# Winter_v2.net
KiCad netlist of a schematic drawn in EAGLE
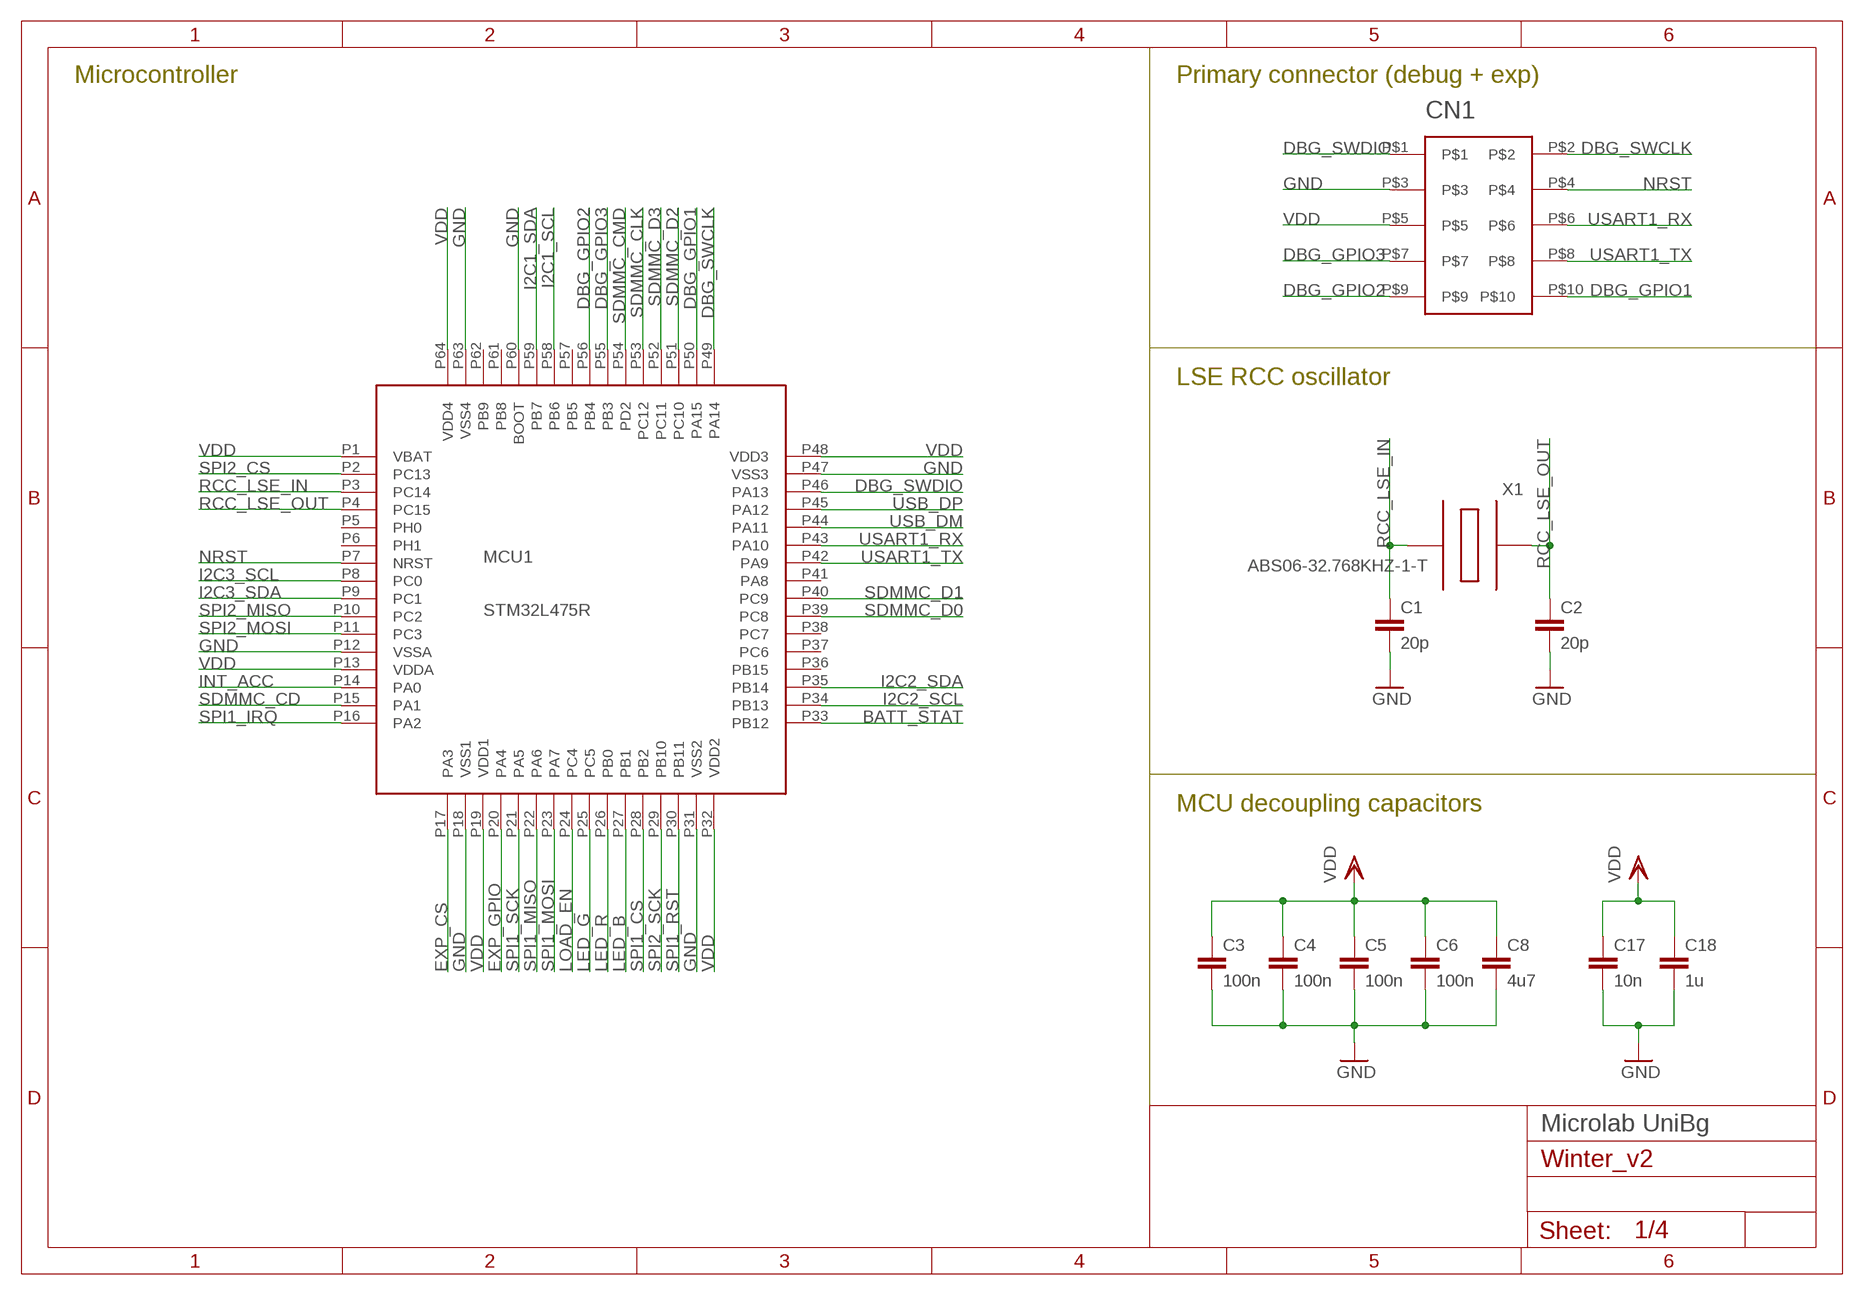
[diagram p0: schematic, sheet 1]
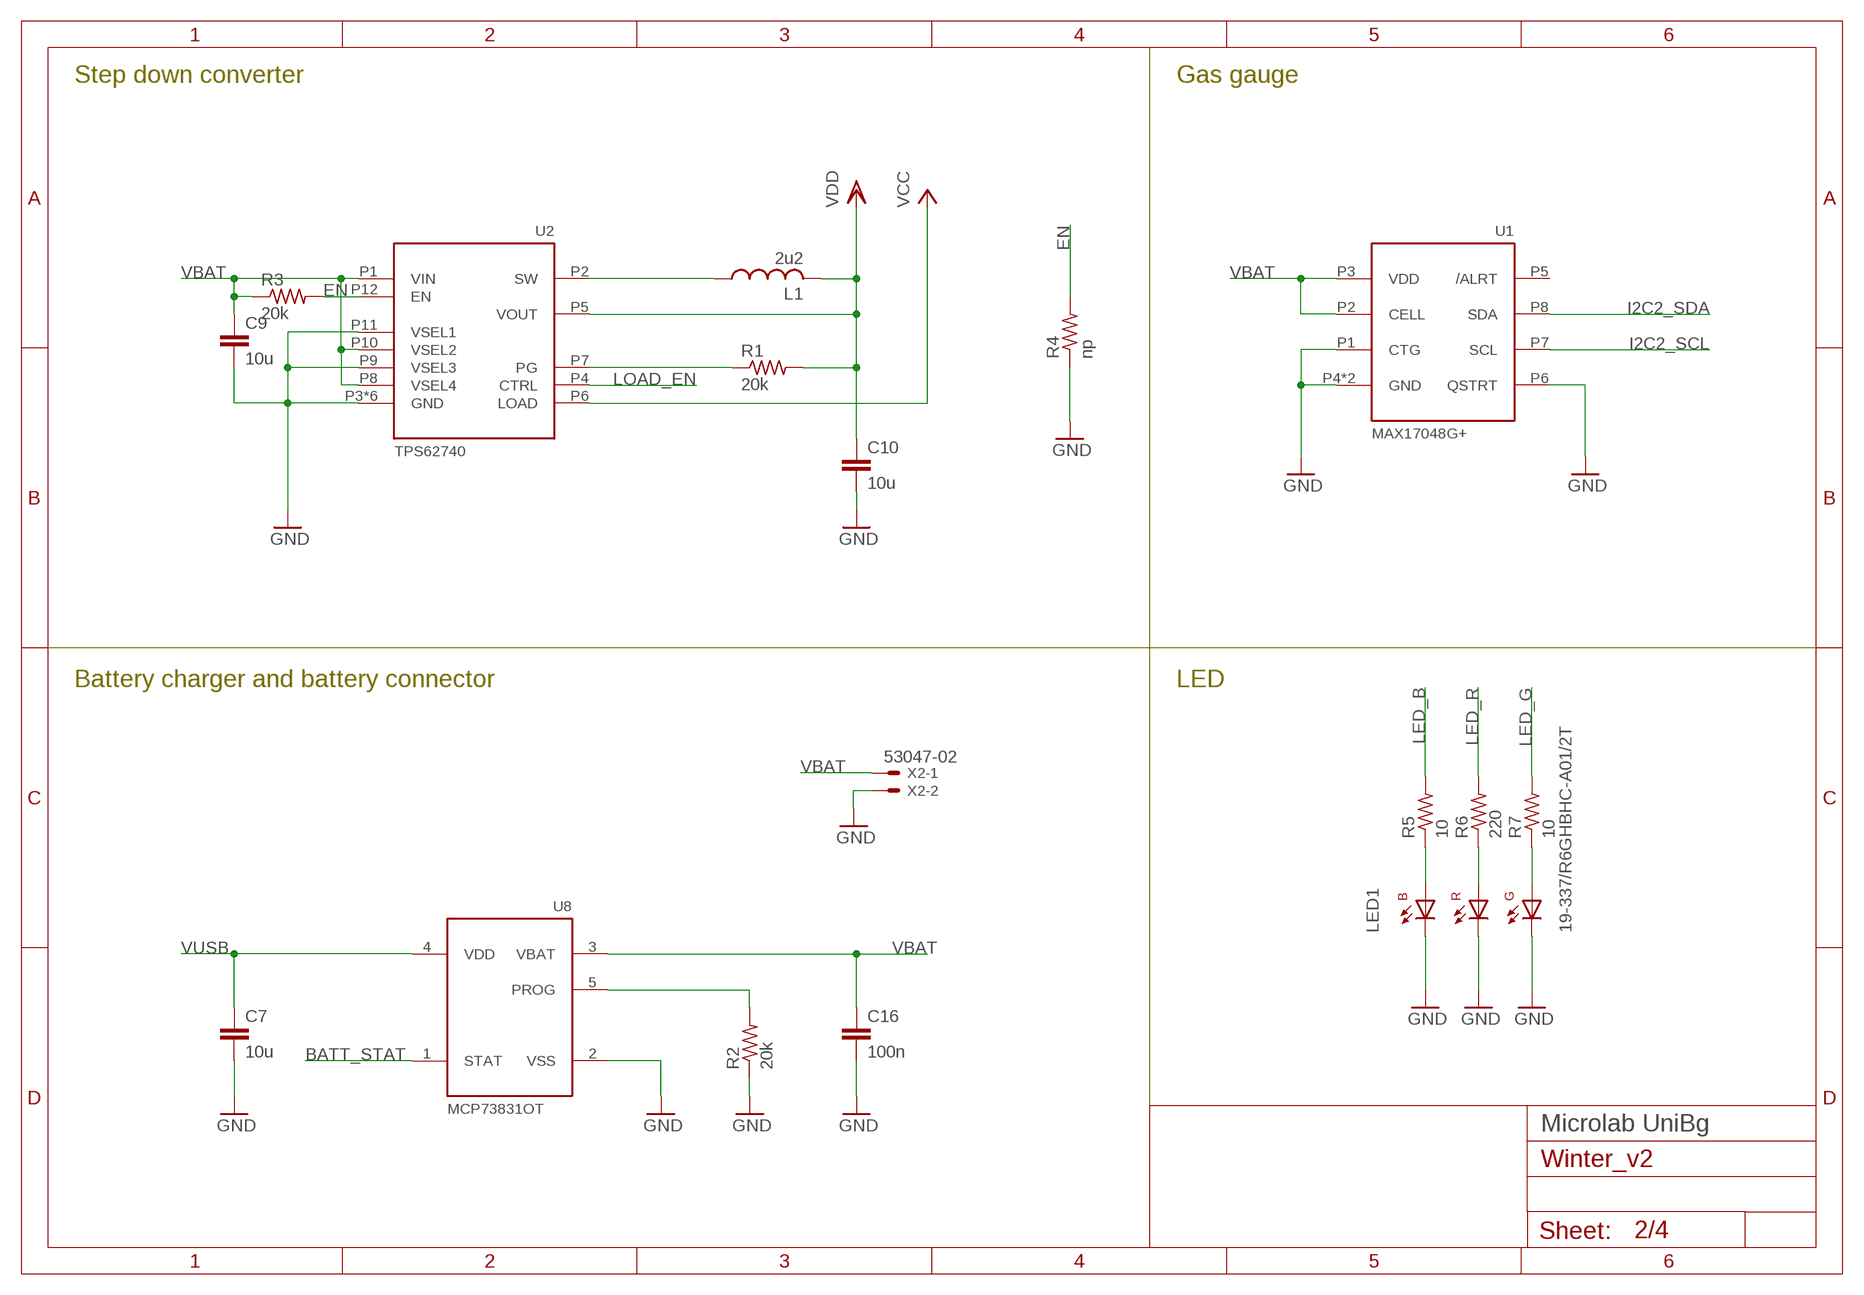
[diagram p1: schematic, sheet 2]
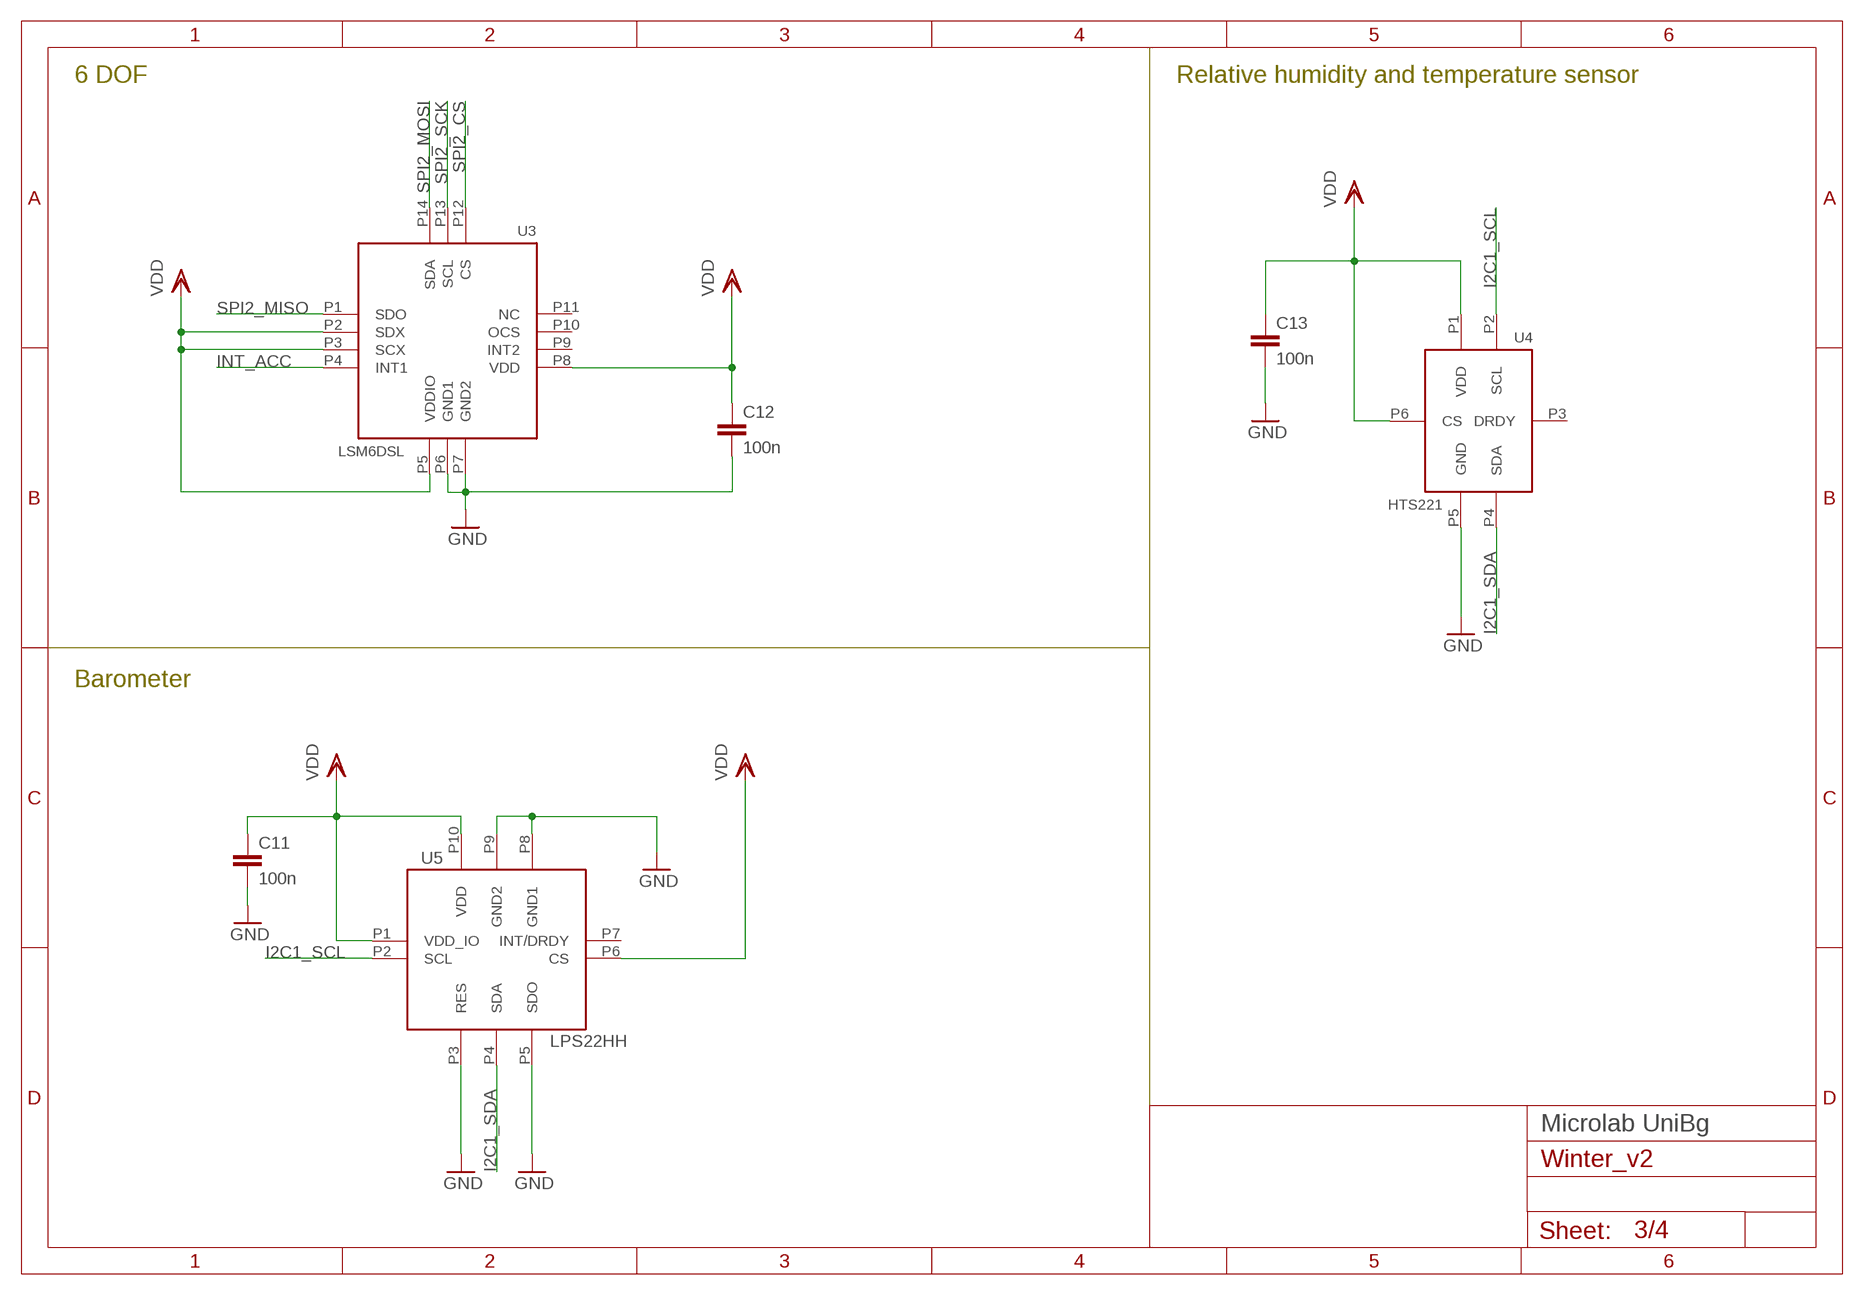
[diagram p2: schematic, sheet 3]
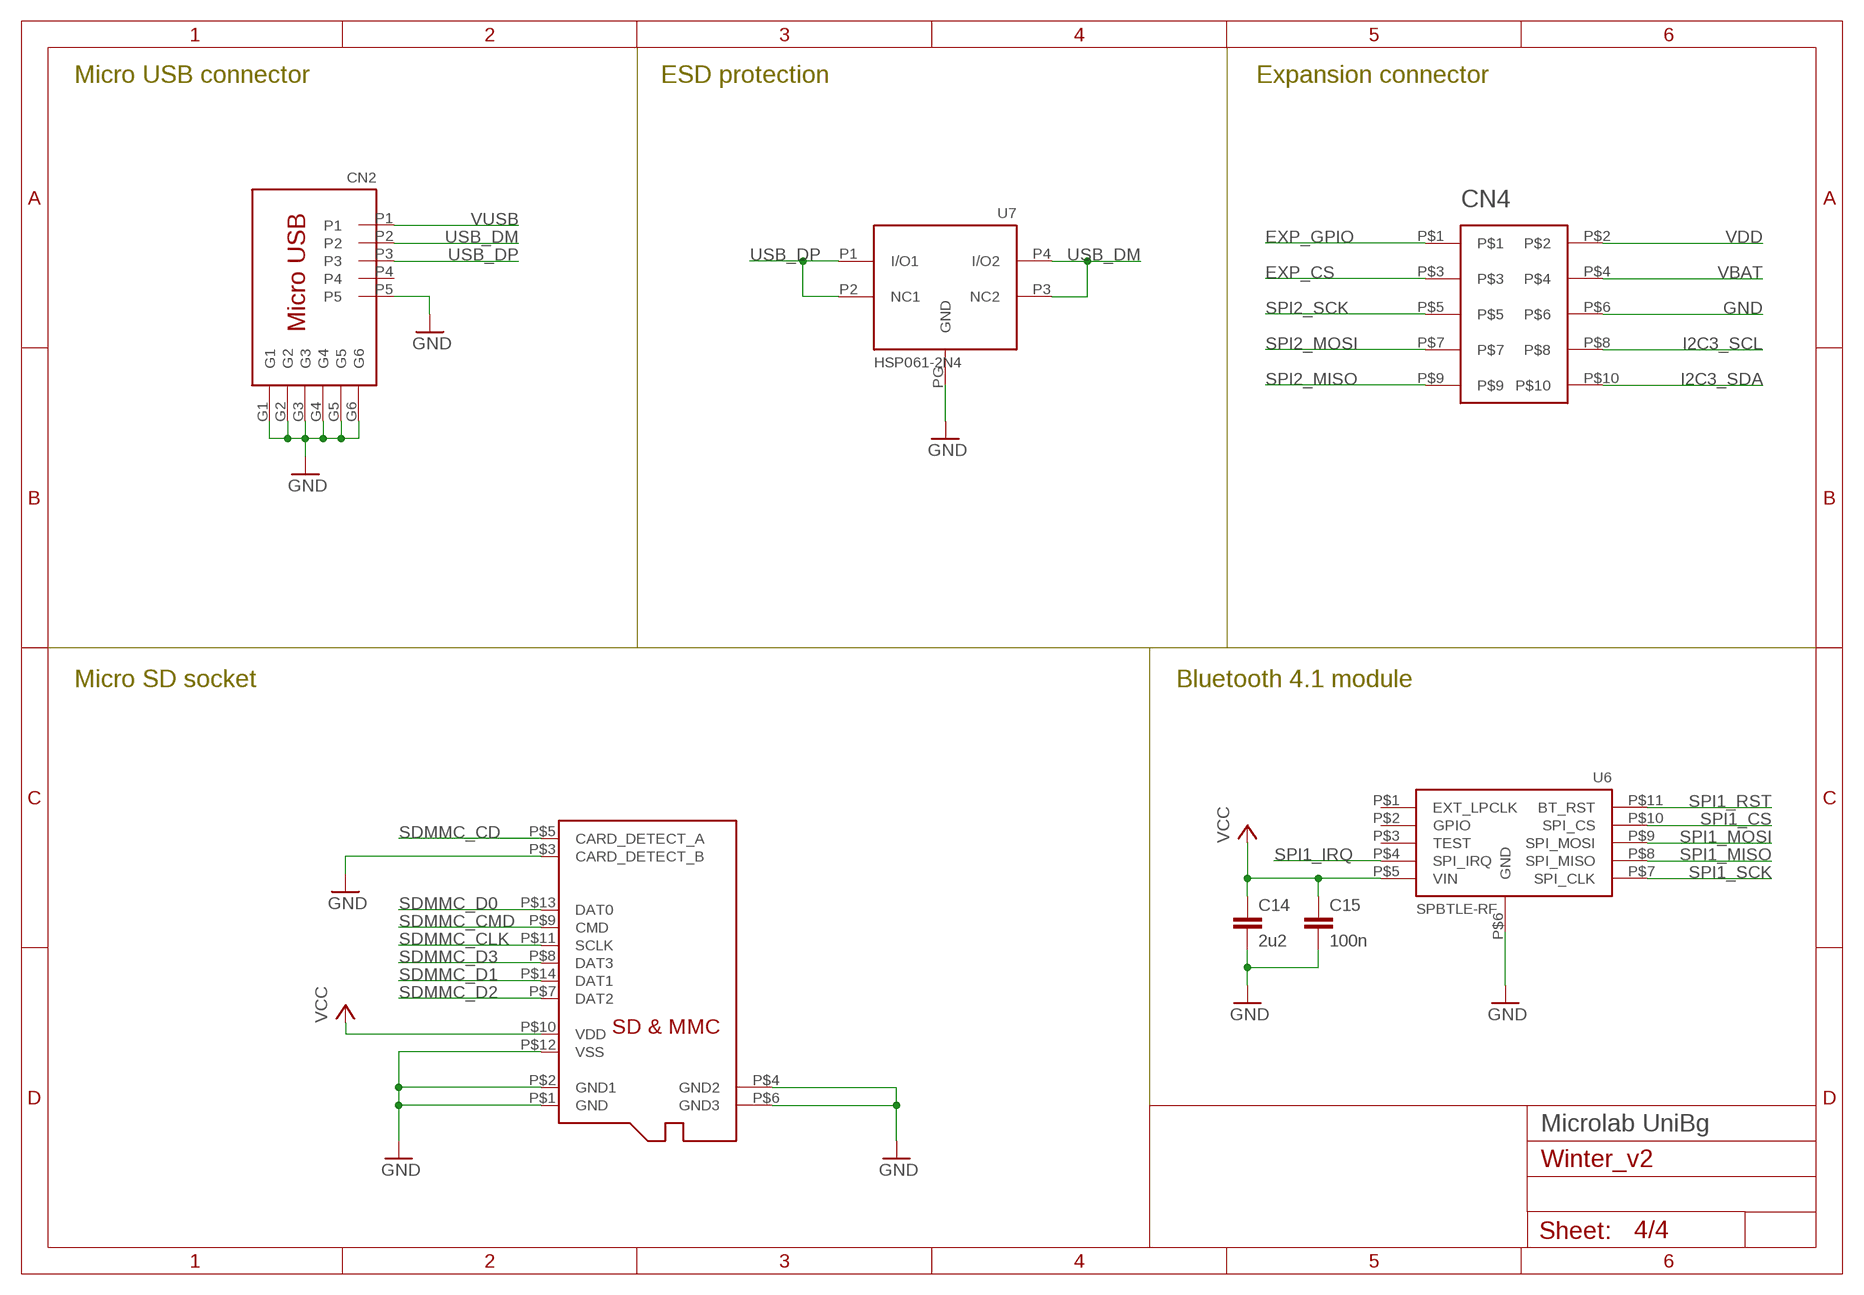
[diagram p3: schematic, sheet 4]

(export (version "E")
  (design (tool "Eeschema 10.0.6"))
  (components
    (comp (ref "C1")
      (value "20p")
      (footprint "eagle-import:C0402")
      (libsource (lib "eagle-import") (part "C0402"))
    )
    (comp (ref "C2")
      (value "20p")
      (footprint "eagle-import:C0402")
      (libsource (lib "eagle-import") (part "C0402"))
    )
    (comp (ref "C3")
      (value "100n")
      (footprint "eagle-import:C0402")
      (libsource (lib "eagle-import") (part "C0402"))
    )
    (comp (ref "C4")
      (value "100n")
      (footprint "eagle-import:C0402")
      (libsource (lib "eagle-import") (part "C0402"))
    )
    (comp (ref "C5")
      (value "100n")
      (footprint "eagle-import:C0402")
      (libsource (lib "eagle-import") (part "C0402"))
    )
    (comp (ref "C6")
      (value "100n")
      (footprint "eagle-import:C0402")
      (libsource (lib "eagle-import") (part "C0402"))
    )
    (comp (ref "C8")
      (value "4u7")
      (footprint "eagle-import:C0402")
      (libsource (lib "eagle-import") (part "C0402"))
    )
    (comp (ref "C17")
      (value "10n")
      (footprint "eagle-import:C0402")
      (libsource (lib "eagle-import") (part "C0402"))
    )
    (comp (ref "C18")
      (value "1u")
      (footprint "eagle-import:C0402")
      (libsource (lib "eagle-import") (part "C0402"))
    )
    (comp (ref "CN1")
      (value "FTSH-105TO")
      (footprint "eagle-import:FTSH-105-XX")
      (libsource (lib "eagle-import") (part "FTSH-105TO"))
    )
    (comp (ref "MCU1")
      (value "STM32L475R")
      (footprint "eagle-import:LQFP64")
      (libsource (lib "eagle-import") (part "STM32L475R"))
    )
    (comp (ref "X1")
      (value "ABS06-32.768KHZ-1-T")
      (footprint "eagle-import:ABS06")
      (libsource (lib "eagle-import") (part "ABS06-32.768KHZ-1-T"))
    )
    (comp (ref "C7")
      (value "10u")
      (footprint "eagle-import:C0603")
      (libsource (lib "eagle-import") (part "C0603"))
    )
    (comp (ref "C9")
      (value "10u")
      (footprint "eagle-import:C0603")
      (libsource (lib "eagle-import") (part "C0603"))
    )
    (comp (ref "C10")
      (value "10u")
      (footprint "eagle-import:C0603")
      (libsource (lib "eagle-import") (part "C0603"))
    )
    (comp (ref "C16")
      (value "100n")
      (footprint "eagle-import:C0402")
      (libsource (lib "eagle-import") (part "C0402"))
    )
    (comp (ref "L1")
      (value "2u2")
      (footprint "eagle-import:C01005")
      (libsource (lib "eagle-import") (part "74479276222C74479276222C"))
    )
    (comp (ref "LED1")
      (value "19-337/R6GHBHC-A01/2T")
      (footprint "eagle-import:19-337_R6GHBHC-A01_2T")
      (libsource (lib "eagle-import") (part "19-337/R6GHBHC-A01/2T"))
    )
    (comp (ref "R1")
      (value "20k")
      (footprint "eagle-import:0402")
      (libsource (lib "eagle-import") (part "R0402"))
    )
    (comp (ref "R2")
      (value "20k")
      (footprint "eagle-import:0402")
      (libsource (lib "eagle-import") (part "R0402"))
    )
    (comp (ref "R3")
      (value "20k")
      (footprint "eagle-import:0402")
      (libsource (lib "eagle-import") (part "R0402"))
    )
    (comp (ref "R4")
      (value "np")
      (footprint "eagle-import:0402")
      (libsource (lib "eagle-import") (part "R0402"))
    )
    (comp (ref "R5")
      (value "10")
      (footprint "eagle-import:0402")
      (libsource (lib "eagle-import") (part "R0402"))
    )
    (comp (ref "R6")
      (value "220")
      (footprint "eagle-import:0402")
      (libsource (lib "eagle-import") (part "R0402"))
    )
    (comp (ref "R7")
      (value "10")
      (footprint "eagle-import:0402")
      (libsource (lib "eagle-import") (part "R0402"))
    )
    (comp (ref "U1")
      (value "MAX17048G+")
      (footprint "eagle-import:TDFN8-2X2")
      (libsource (lib "eagle-import") (part "MAX17048G+"))
    )
    (comp (ref "U2")
      (value "TPS62740")
      (footprint "eagle-import:R-PWSON-N12")
      (libsource (lib "eagle-import") (part "TPS62740"))
    )
    (comp (ref "U8")
      (value "MCP73831OT")
      (footprint "eagle-import:SOT23-5L")
      (libsource (lib "eagle-import") (part "MCP73831OT"))
    )
    (comp (ref "X2")
      (value "53047-02")
      (footprint "eagle-import:53047-02")
      (fields (field (name "MF") "MOLEX") (field (name "MPN") "53047-0210"))
      (libsource (lib "eagle-import") (part "53?-02047"))
    )
    (comp (ref "C11")
      (value "100n")
      (footprint "eagle-import:C0402")
      (libsource (lib "eagle-import") (part "C0402"))
    )
    (comp (ref "C12")
      (value "100n")
      (footprint "eagle-import:C0402")
      (libsource (lib "eagle-import") (part "C0402"))
    )
    (comp (ref "C13")
      (value "100n")
      (footprint "eagle-import:C0402")
      (libsource (lib "eagle-import") (part "C0402"))
    )
    (comp (ref "U3")
      (value "LSM6DSL")
      (footprint "eagle-import:LGA-14L")
      (libsource (lib "eagle-import") (part "LSM6DSL"))
    )
    (comp (ref "U4")
      (value "HTS221")
      (footprint "eagle-import:HCLGA-6L")
      (libsource (lib "eagle-import") (part "HTS221"))
    )
    (comp (ref "U5")
      (value "LPS22HH")
      (footprint "eagle-import:HLGA-10L")
      (libsource (lib "eagle-import") (part "LPS22HH"))
    )
    (comp (ref "C14")
      (value "2u2")
      (footprint "eagle-import:C0402")
      (libsource (lib "eagle-import") (part "C0402"))
    )
    (comp (ref "C15")
      (value "100n")
      (footprint "eagle-import:C0402")
      (libsource (lib "eagle-import") (part "C0402"))
    )
    (comp (ref "CN2")
      (value "USB3075")
      (footprint "eagle-import:USB3075")
      (libsource (lib "eagle-import") (part "USB3075"))
    )
    (comp (ref "CN3")
      (value "MICRO_SD-5025700893")
      (footprint "eagle-import:5025700893")
      (libsource (lib "eagle-import") (part "MICRO_SD-5025700893"))
    )
    (comp (ref "CN4")
      (value "FTSH-105TO")
      (footprint "eagle-import:FTSH-105-XX")
      (libsource (lib "eagle-import") (part "FTSH-105TO"))
    )
    (comp (ref "U6")
      (value "SPBTLE-RF")
      (footprint "eagle-import:SPBTLE-RF")
      (libsource (lib "eagle-import") (part "SPBTLE-RF"))
    )
    (comp (ref "U7")
      (value "HSP061-2N4")
      (footprint "eagle-import:μQFN-4L")
      (libsource (lib "eagle-import") (part "HSP061-2N4"))
    )
  )
  (nets
    (net (code "1") (name "BATT_STAT") (class "Default")
      (node (ref "MCU1") (pin "P33") (pinfunction "PB12_P33") (pintype "bidirectional"))
      (node (ref "U8") (pin "1") (pinfunction "STAT_1") (pintype "bidirectional"))
    )
    (net (code "2") (name "DBG_GPIO1") (class "Default")
      (node (ref "CN1") (pin "P$10") (pinfunction "P$10_P$10") (pintype "bidirectional"))
      (node (ref "MCU1") (pin "P50") (pinfunction "PA15_P50") (pintype "bidirectional"))
    )
    (net (code "3") (name "DBG_GPIO2") (class "Default")
      (node (ref "CN1") (pin "P$9") (pinfunction "P$9_P$9") (pintype "bidirectional"))
      (node (ref "MCU1") (pin "P56") (pinfunction "PB4_P56") (pintype "bidirectional"))
    )
    (net (code "4") (name "DBG_GPIO3") (class "Default")
      (node (ref "CN1") (pin "P$7") (pinfunction "P$7_P$7") (pintype "bidirectional"))
      (node (ref "MCU1") (pin "P55") (pinfunction "PB3_P55") (pintype "bidirectional"))
    )
    (net (code "5") (name "DBG_SWCLK") (class "Default")
      (node (ref "CN1") (pin "P$2") (pinfunction "P$2_P$2") (pintype "bidirectional"))
      (node (ref "MCU1") (pin "P49") (pinfunction "PA14_P49") (pintype "bidirectional"))
    )
    (net (code "6") (name "DBG_SWDIO") (class "Default")
      (node (ref "CN1") (pin "P$1") (pinfunction "P$1_P$1") (pintype "bidirectional"))
      (node (ref "MCU1") (pin "P46") (pinfunction "PA13_P46") (pintype "bidirectional"))
    )
    (net (code "7") (name "EN") (class "Default")
      (node (ref "R3") (pin "P$2") (pinfunction "2_P$2") (pintype "passive"))
      (node (ref "R4") (pin "P$2") (pinfunction "2_P$2") (pintype "passive"))
      (node (ref "U2") (pin "P12") (pinfunction "EN_P12") (pintype "bidirectional"))
    )
    (net (code "8") (name "EXP_CS") (class "Default")
      (node (ref "CN4") (pin "P$3") (pinfunction "P$3_P$3") (pintype "bidirectional"))
      (node (ref "MCU1") (pin "P17") (pinfunction "PA3_P17") (pintype "bidirectional"))
    )
    (net (code "9") (name "EXP_GPIO") (class "Default")
      (node (ref "CN4") (pin "P$1") (pinfunction "P$1_P$1") (pintype "bidirectional"))
      (node (ref "MCU1") (pin "P20") (pinfunction "PA4_P20") (pintype "bidirectional"))
    )
    (net (code "10") (name "GND") (class "Default")
      (node (ref "C1") (pin "P$2") (pinfunction "2_P$2") (pintype "passive"))
      (node (ref "C10") (pin "P$2") (pinfunction "2_P$2") (pintype "passive"))
      (node (ref "C11") (pin "P$2") (pinfunction "2_P$2") (pintype "passive"))
      (node (ref "C12") (pin "P$2") (pinfunction "2_P$2") (pintype "passive"))
      (node (ref "C13") (pin "P$2") (pinfunction "2_P$2") (pintype "passive"))
      (node (ref "C14") (pin "P$2") (pinfunction "2_P$2") (pintype "passive"))
      (node (ref "C15") (pin "P$2") (pinfunction "2_P$2") (pintype "passive"))
      (node (ref "C16") (pin "P$2") (pinfunction "2_P$2") (pintype "passive"))
      (node (ref "C17") (pin "P$2") (pinfunction "2_P$2") (pintype "passive"))
      (node (ref "C18") (pin "P$2") (pinfunction "2_P$2") (pintype "passive"))
      (node (ref "C2") (pin "P$2") (pinfunction "2_P$2") (pintype "passive"))
      (node (ref "C3") (pin "P$2") (pinfunction "2_P$2") (pintype "passive"))
      (node (ref "C4") (pin "P$2") (pinfunction "2_P$2") (pintype "passive"))
      (node (ref "C5") (pin "P$2") (pinfunction "2_P$2") (pintype "passive"))
      (node (ref "C6") (pin "P$2") (pinfunction "2_P$2") (pintype "passive"))
      (node (ref "C7") (pin "P$2") (pinfunction "2_P$2") (pintype "passive"))
      (node (ref "C8") (pin "P$2") (pinfunction "2_P$2") (pintype "passive"))
      (node (ref "C9") (pin "P$2") (pinfunction "2_P$2") (pintype "passive"))
      (node (ref "CN1") (pin "P$3") (pinfunction "P$3_P$3") (pintype "bidirectional"))
      (node (ref "CN2") (pin "G1") (pinfunction "G1_G1") (pintype "bidirectional"))
      (node (ref "CN2") (pin "G2") (pinfunction "G2_G2") (pintype "bidirectional"))
      (node (ref "CN2") (pin "G3") (pinfunction "G3_G3") (pintype "bidirectional"))
      (node (ref "CN2") (pin "G4") (pinfunction "G4_G4") (pintype "bidirectional"))
      (node (ref "CN2") (pin "G5") (pinfunction "G5_G5") (pintype "bidirectional"))
      (node (ref "CN2") (pin "G6") (pinfunction "G6_G6") (pintype "bidirectional"))
      (node (ref "CN2") (pin "P5") (pinfunction "P5_P5") (pintype "bidirectional"))
      (node (ref "CN3") (pin "P$1") (pinfunction "GND_P$1") (pintype "power_in"))
      (node (ref "CN3") (pin "P$12") (pinfunction "VSS_P$12") (pintype "power_in"))
      (node (ref "CN3") (pin "P$2") (pinfunction "GND1_P$2") (pintype "power_in"))
      (node (ref "CN3") (pin "P$3") (pinfunction "CARD_DETECT_B_P$3") (pintype "passive"))
      (node (ref "CN3") (pin "P$4") (pinfunction "GND2_P$4") (pintype "bidirectional"))
      (node (ref "CN3") (pin "P$6") (pinfunction "GND3_P$6") (pintype "bidirectional"))
      (node (ref "CN4") (pin "P$6") (pinfunction "P$6_P$6") (pintype "bidirectional"))
      (node (ref "LED1") (pin "P$1") (pinfunction "CB_P$1") (pintype "passive"))
      (node (ref "LED1") (pin "P$2") (pinfunction "CR_P$2") (pintype "passive"))
      (node (ref "LED1") (pin "P$3") (pinfunction "CG_P$3") (pintype "passive"))
      (node (ref "MCU1") (pin "P12") (pinfunction "VSSA_P12") (pintype "bidirectional"))
      (node (ref "MCU1") (pin "P18") (pinfunction "VSS1_P18") (pintype "bidirectional"))
      (node (ref "MCU1") (pin "P31") (pinfunction "VSS2_P31") (pintype "bidirectional"))
      (node (ref "MCU1") (pin "P47") (pinfunction "VSS3_P47") (pintype "bidirectional"))
      (node (ref "MCU1") (pin "P60") (pinfunction "BOOT_P60") (pintype "bidirectional"))
      (node (ref "MCU1") (pin "P63") (pinfunction "VSS4_P63") (pintype "bidirectional"))
      (node (ref "R2") (pin "P$1") (pinfunction "1_P$1") (pintype "passive"))
      (node (ref "R4") (pin "P$1") (pinfunction "1_P$1") (pintype "passive"))
      (node (ref "U1") (pin "P1") (pinfunction "CTG_P1") (pintype "bidirectional"))
      (node (ref "U1") (pin "P4") (pinfunction "GND_P4") (pintype "bidirectional"))
      (node (ref "U1") (pin "P6") (pinfunction "QSTRT_P6") (pintype "bidirectional"))
      (node (ref "U1") (pin "P9") (pinfunction "GND_P9") (pintype "bidirectional"))
      (node (ref "U2") (pin "P11") (pinfunction "VSEL1_P11") (pintype "bidirectional"))
      (node (ref "U2") (pin "P3") (pinfunction "GND_P3") (pintype "bidirectional"))
      (node (ref "U2") (pin "P9") (pinfunction "VSEL3_P9") (pintype "bidirectional"))
      (node (ref "U2") (pin "PG1") (pinfunction "GND_PG1") (pintype "bidirectional"))
      (node (ref "U2") (pin "PG2") (pinfunction "GND_PG2") (pintype "bidirectional"))
      (node (ref "U2") (pin "PG3") (pinfunction "GND_PG3") (pintype "bidirectional"))
      (node (ref "U2") (pin "PG4") (pinfunction "GND_PG4") (pintype "bidirectional"))
      (node (ref "U2") (pin "PG5") (pinfunction "GND_PG5") (pintype "bidirectional"))
      (node (ref "U3") (pin "P6") (pinfunction "GND1_P6") (pintype "bidirectional"))
      (node (ref "U3") (pin "P7") (pinfunction "GND2_P7") (pintype "bidirectional"))
      (node (ref "U4") (pin "P5") (pinfunction "GND_P5") (pintype "bidirectional"))
      (node (ref "U5") (pin "P3") (pinfunction "RES_P3") (pintype "bidirectional"))
      (node (ref "U5") (pin "P5") (pinfunction "SDO_P5") (pintype "bidirectional"))
      (node (ref "U5") (pin "P8") (pinfunction "GND1_P8") (pintype "bidirectional"))
      (node (ref "U5") (pin "P9") (pinfunction "GND2_P9") (pintype "bidirectional"))
      (node (ref "U6") (pin "P$6") (pinfunction "GND_P$6") (pintype "bidirectional"))
      (node (ref "U7") (pin "PG") (pinfunction "GND_PG") (pintype "bidirectional"))
      (node (ref "U8") (pin "2") (pinfunction "VSS_2") (pintype "bidirectional"))
      (node (ref "X2") (pin "2") (pinfunction "S_2") (pintype "passive"))
    )
    (net (code "11") (name "I2C1_SCL") (class "Default")
      (node (ref "MCU1") (pin "P58") (pinfunction "PB6_P58") (pintype "bidirectional"))
      (node (ref "U4") (pin "P2") (pinfunction "SCL_P2") (pintype "bidirectional"))
      (node (ref "U5") (pin "P2") (pinfunction "SCL_P2") (pintype "bidirectional"))
    )
    (net (code "12") (name "I2C1_SDA") (class "Default")
      (node (ref "MCU1") (pin "P59") (pinfunction "PB7_P59") (pintype "bidirectional"))
      (node (ref "U4") (pin "P4") (pinfunction "SDA_P4") (pintype "bidirectional"))
      (node (ref "U5") (pin "P4") (pinfunction "SDA_P4") (pintype "bidirectional"))
    )
    (net (code "13") (name "I2C2_SCL") (class "Default")
      (node (ref "MCU1") (pin "P34") (pinfunction "PB13_P34") (pintype "bidirectional"))
      (node (ref "U1") (pin "P7") (pinfunction "SCL_P7") (pintype "bidirectional"))
    )
    (net (code "14") (name "I2C2_SDA") (class "Default")
      (node (ref "MCU1") (pin "P35") (pinfunction "PB14_P35") (pintype "bidirectional"))
      (node (ref "U1") (pin "P8") (pinfunction "SDA_P8") (pintype "bidirectional"))
    )
    (net (code "15") (name "I2C3_SCL") (class "Default")
      (node (ref "CN4") (pin "P$8") (pinfunction "P$8_P$8") (pintype "bidirectional"))
      (node (ref "MCU1") (pin "P8") (pinfunction "PC0_P8") (pintype "bidirectional"))
    )
    (net (code "16") (name "I2C3_SDA") (class "Default")
      (node (ref "CN4") (pin "P$10") (pinfunction "P$10_P$10") (pintype "bidirectional"))
      (node (ref "MCU1") (pin "P9") (pinfunction "PC1_P9") (pintype "bidirectional"))
    )
    (net (code "17") (name "INT_ACC") (class "Default")
      (node (ref "MCU1") (pin "P14") (pinfunction "PA0_P14") (pintype "bidirectional"))
      (node (ref "U3") (pin "P4") (pinfunction "INT1_P4") (pintype "bidirectional"))
    )
    (net (code "18") (name "LED_B") (class "Default")
      (node (ref "MCU1") (pin "P27") (pinfunction "PB1_P27") (pintype "bidirectional"))
      (node (ref "R5") (pin "P$2") (pinfunction "2_P$2") (pintype "passive"))
    )
    (net (code "19") (name "LED_G") (class "Default")
      (node (ref "MCU1") (pin "P25") (pinfunction "PC5_P25") (pintype "bidirectional"))
      (node (ref "R7") (pin "P$2") (pinfunction "2_P$2") (pintype "passive"))
    )
    (net (code "20") (name "LED_R") (class "Default")
      (node (ref "MCU1") (pin "P26") (pinfunction "PB0_P26") (pintype "bidirectional"))
      (node (ref "R6") (pin "P$2") (pinfunction "2_P$2") (pintype "passive"))
    )
    (net (code "21") (name "LOAD_EN") (class "Default")
      (node (ref "MCU1") (pin "P24") (pinfunction "PC4_P24") (pintype "bidirectional"))
      (node (ref "U2") (pin "P4") (pinfunction "CTRL_P4") (pintype "bidirectional"))
    )
    (net (code "22") (name "NRST") (class "Default")
      (node (ref "CN1") (pin "P$4") (pinfunction "P$4_P$4") (pintype "bidirectional"))
      (node (ref "MCU1") (pin "P7") (pinfunction "NRST_P7") (pintype "bidirectional"))
    )
    (net (code "23") (name "Net-(L1-1)") (class "Default")
      (node (ref "L1") (pin "P$1") (pinfunction "1_P$1") (pintype "passive"))
      (node (ref "U2") (pin "P2") (pinfunction "SW_P2") (pintype "bidirectional"))
    )
    (net (code "24") (name "Net-(LED1-AB)") (class "Default")
      (node (ref "LED1") (pin "P$4") (pinfunction "AB_P$4") (pintype "passive"))
      (node (ref "R5") (pin "P$1") (pinfunction "1_P$1") (pintype "passive"))
    )
    (net (code "25") (name "Net-(LED1-AG)") (class "Default")
      (node (ref "LED1") (pin "P$6") (pinfunction "AG_P$6") (pintype "passive"))
      (node (ref "R7") (pin "P$1") (pinfunction "1_P$1") (pintype "passive"))
    )
    (net (code "26") (name "Net-(LED1-AR)") (class "Default")
      (node (ref "LED1") (pin "P$5") (pinfunction "AR_P$5") (pintype "passive"))
      (node (ref "R6") (pin "P$1") (pinfunction "1_P$1") (pintype "passive"))
    )
    (net (code "27") (name "Net-(R1-1)") (class "Default")
      (node (ref "R1") (pin "P$1") (pinfunction "1_P$1") (pintype "passive"))
      (node (ref "U2") (pin "P7") (pinfunction "PG_P7") (pintype "bidirectional"))
    )
    (net (code "28") (name "Net-(R2-2)") (class "Default")
      (node (ref "R2") (pin "P$2") (pinfunction "2_P$2") (pintype "passive"))
      (node (ref "U8") (pin "5") (pinfunction "PROG_5") (pintype "bidirectional"))
    )
    (net (code "29") (name "RCC_LSE_IN") (class "Default")
      (node (ref "C1") (pin "P$1") (pinfunction "1_P$1") (pintype "passive"))
      (node (ref "MCU1") (pin "P3") (pinfunction "PC14_P3") (pintype "bidirectional"))
      (node (ref "X1") (pin "P1") (pinfunction "P1_P1") (pintype "bidirectional"))
    )
    (net (code "30") (name "RCC_LSE_OUT") (class "Default")
      (node (ref "C2") (pin "P$1") (pinfunction "1_P$1") (pintype "passive"))
      (node (ref "MCU1") (pin "P4") (pinfunction "PC15_P4") (pintype "bidirectional"))
      (node (ref "X1") (pin "P2") (pinfunction "P2_P2") (pintype "bidirectional"))
    )
    (net (code "31") (name "SDMMC_CD") (class "Default")
      (node (ref "CN3") (pin "P$5") (pinfunction "CARD_DETECT_A_P$5") (pintype "passive"))
      (node (ref "MCU1") (pin "P15") (pinfunction "PA1_P15") (pintype "bidirectional"))
    )
    (net (code "32") (name "SDMMC_CLK") (class "Default")
      (node (ref "CN3") (pin "P$11") (pinfunction "SCLK_P$11") (pintype "input"))
      (node (ref "MCU1") (pin "P53") (pinfunction "PC12_P53") (pintype "bidirectional"))
    )
    (net (code "33") (name "SDMMC_CMD") (class "Default")
      (node (ref "CN3") (pin "P$9") (pinfunction "CMD_P$9") (pintype "input"))
      (node (ref "MCU1") (pin "P54") (pinfunction "PD2_P54") (pintype "bidirectional"))
    )
    (net (code "34") (name "SDMMC_D0") (class "Default")
      (node (ref "CN3") (pin "P$13") (pinfunction "DAT0_P$13") (pintype "output"))
      (node (ref "MCU1") (pin "P39") (pinfunction "PC8_P39") (pintype "bidirectional"))
    )
    (net (code "35") (name "SDMMC_D1") (class "Default")
      (node (ref "CN3") (pin "P$14") (pinfunction "DAT1_P$14") (pintype "bidirectional"))
      (node (ref "MCU1") (pin "P40") (pinfunction "PC9_P40") (pintype "bidirectional"))
    )
    (net (code "36") (name "SDMMC_D2") (class "Default")
      (node (ref "CN3") (pin "P$7") (pinfunction "DAT2_P$7") (pintype "bidirectional"))
      (node (ref "MCU1") (pin "P51") (pinfunction "PC10_P51") (pintype "bidirectional"))
    )
    (net (code "37") (name "SDMMC_D3") (class "Default")
      (node (ref "CN3") (pin "P$8") (pinfunction "DAT3_P$8") (pintype "input"))
      (node (ref "MCU1") (pin "P52") (pinfunction "PC11_P52") (pintype "bidirectional"))
    )
    (net (code "38") (name "SPI1_CS") (class "Default")
      (node (ref "MCU1") (pin "P28") (pinfunction "PB2_P28") (pintype "bidirectional"))
      (node (ref "U6") (pin "P$10") (pinfunction "SPI_CS_P$10") (pintype "bidirectional"))
    )
    (net (code "39") (name "SPI1_IRQ") (class "Default")
      (node (ref "MCU1") (pin "P16") (pinfunction "PA2_P16") (pintype "bidirectional"))
      (node (ref "U6") (pin "P$4") (pinfunction "SPI_IRQ_P$4") (pintype "bidirectional"))
    )
    (net (code "40") (name "SPI1_MISO") (class "Default")
      (node (ref "MCU1") (pin "P22") (pinfunction "PA6_P22") (pintype "bidirectional"))
      (node (ref "U6") (pin "P$8") (pinfunction "SPI_MISO_P$8") (pintype "bidirectional"))
    )
    (net (code "41") (name "SPI1_MOSI") (class "Default")
      (node (ref "MCU1") (pin "P23") (pinfunction "PA7_P23") (pintype "bidirectional"))
      (node (ref "U6") (pin "P$9") (pinfunction "SPI_MOSI_P$9") (pintype "bidirectional"))
    )
    (net (code "42") (name "SPI1_RST") (class "Default")
      (node (ref "MCU1") (pin "P30") (pinfunction "PB11_P30") (pintype "bidirectional"))
      (node (ref "U6") (pin "P$11") (pinfunction "BT_RST_P$11") (pintype "bidirectional"))
    )
    (net (code "43") (name "SPI1_SCK") (class "Default")
      (node (ref "MCU1") (pin "P21") (pinfunction "PA5_P21") (pintype "bidirectional"))
      (node (ref "U6") (pin "P$7") (pinfunction "SPI_CLK_P$7") (pintype "bidirectional"))
    )
    (net (code "44") (name "SPI2_CS") (class "Default")
      (node (ref "MCU1") (pin "P2") (pinfunction "PC13_P2") (pintype "bidirectional"))
      (node (ref "U3") (pin "P12") (pinfunction "CS_P12") (pintype "bidirectional"))
    )
    (net (code "45") (name "SPI2_MISO") (class "Default")
      (node (ref "CN4") (pin "P$9") (pinfunction "P$9_P$9") (pintype "bidirectional"))
      (node (ref "MCU1") (pin "P10") (pinfunction "PC2_P10") (pintype "bidirectional"))
      (node (ref "U3") (pin "P1") (pinfunction "SDO_P1") (pintype "bidirectional"))
    )
    (net (code "46") (name "SPI2_MOSI") (class "Default")
      (node (ref "CN4") (pin "P$7") (pinfunction "P$7_P$7") (pintype "bidirectional"))
      (node (ref "MCU1") (pin "P11") (pinfunction "PC3_P11") (pintype "bidirectional"))
      (node (ref "U3") (pin "P14") (pinfunction "SDA_P14") (pintype "bidirectional"))
    )
    (net (code "47") (name "SPI2_SCK") (class "Default")
      (node (ref "CN4") (pin "P$5") (pinfunction "P$5_P$5") (pintype "bidirectional"))
      (node (ref "MCU1") (pin "P29") (pinfunction "PB10_P29") (pintype "bidirectional"))
      (node (ref "U3") (pin "P13") (pinfunction "SCL_P13") (pintype "bidirectional"))
    )
    (net (code "48") (name "USART1_RX") (class "Default")
      (node (ref "CN1") (pin "P$6") (pinfunction "P$6_P$6") (pintype "bidirectional"))
      (node (ref "MCU1") (pin "P43") (pinfunction "PA10_P43") (pintype "bidirectional"))
    )
    (net (code "49") (name "USART1_TX") (class "Default")
      (node (ref "CN1") (pin "P$8") (pinfunction "P$8_P$8") (pintype "bidirectional"))
      (node (ref "MCU1") (pin "P42") (pinfunction "PA9_P42") (pintype "bidirectional"))
    )
    (net (code "50") (name "USB_DM") (class "Default")
      (node (ref "CN2") (pin "P2") (pinfunction "P2_P2") (pintype "bidirectional"))
      (node (ref "MCU1") (pin "P44") (pinfunction "PA11_P44") (pintype "bidirectional"))
      (node (ref "U7") (pin "P3") (pinfunction "NC2_P3") (pintype "bidirectional"))
      (node (ref "U7") (pin "P4") (pinfunction "I/O2_P4") (pintype "bidirectional"))
    )
    (net (code "51") (name "USB_DP") (class "Default")
      (node (ref "CN2") (pin "P3") (pinfunction "P3_P3") (pintype "bidirectional"))
      (node (ref "MCU1") (pin "P45") (pinfunction "PA12_P45") (pintype "bidirectional"))
      (node (ref "U7") (pin "P1") (pinfunction "I/O1_P1") (pintype "bidirectional"))
      (node (ref "U7") (pin "P2") (pinfunction "NC1_P2") (pintype "bidirectional"))
    )
    (net (code "52") (name "VBAT") (class "Default")
      (node (ref "C16") (pin "P$1") (pinfunction "1_P$1") (pintype "passive"))
      (node (ref "C9") (pin "P$1") (pinfunction "1_P$1") (pintype "passive"))
      (node (ref "CN4") (pin "P$4") (pinfunction "P$4_P$4") (pintype "bidirectional"))
      (node (ref "R3") (pin "P$1") (pinfunction "1_P$1") (pintype "passive"))
      (node (ref "U1") (pin "P2") (pinfunction "CELL_P2") (pintype "bidirectional"))
      (node (ref "U1") (pin "P3") (pinfunction "VDD_P3") (pintype "bidirectional"))
      (node (ref "U2") (pin "P1") (pinfunction "VIN_P1") (pintype "bidirectional"))
      (node (ref "U2") (pin "P10") (pinfunction "VSEL2_P10") (pintype "bidirectional"))
      (node (ref "U2") (pin "P8") (pinfunction "VSEL4_P8") (pintype "bidirectional"))
      (node (ref "U8") (pin "3") (pinfunction "VBAT_3") (pintype "bidirectional"))
      (node (ref "X2") (pin "1") (pinfunction "S_1") (pintype "passive"))
    )
    (net (code "53") (name "VCC") (class "Default")
      (node (ref "C14") (pin "P$1") (pinfunction "1_P$1") (pintype "passive"))
      (node (ref "C15") (pin "P$1") (pinfunction "1_P$1") (pintype "passive"))
      (node (ref "CN3") (pin "P$10") (pinfunction "VDD_P$10") (pintype "power_in"))
      (node (ref "U2") (pin "P6") (pinfunction "LOAD_P6") (pintype "bidirectional"))
      (node (ref "U6") (pin "P$5") (pinfunction "VIN_P$5") (pintype "bidirectional"))
    )
    (net (code "54") (name "VDD") (class "Default")
      (node (ref "C10") (pin "P$1") (pinfunction "1_P$1") (pintype "passive"))
      (node (ref "C11") (pin "P$1") (pinfunction "1_P$1") (pintype "passive"))
      (node (ref "C12") (pin "P$1") (pinfunction "1_P$1") (pintype "passive"))
      (node (ref "C13") (pin "P$1") (pinfunction "1_P$1") (pintype "passive"))
      (node (ref "C17") (pin "P$1") (pinfunction "1_P$1") (pintype "passive"))
      (node (ref "C18") (pin "P$1") (pinfunction "1_P$1") (pintype "passive"))
      (node (ref "C3") (pin "P$1") (pinfunction "1_P$1") (pintype "passive"))
      (node (ref "C4") (pin "P$1") (pinfunction "1_P$1") (pintype "passive"))
      (node (ref "C5") (pin "P$1") (pinfunction "1_P$1") (pintype "passive"))
      (node (ref "C6") (pin "P$1") (pinfunction "1_P$1") (pintype "passive"))
      (node (ref "C8") (pin "P$1") (pinfunction "1_P$1") (pintype "passive"))
      (node (ref "CN1") (pin "P$5") (pinfunction "P$5_P$5") (pintype "bidirectional"))
      (node (ref "CN4") (pin "P$2") (pinfunction "P$2_P$2") (pintype "bidirectional"))
      (node (ref "L1") (pin "P$2") (pinfunction "2_P$2") (pintype "passive"))
      (node (ref "MCU1") (pin "P1") (pinfunction "VBAT_P1") (pintype "bidirectional"))
      (node (ref "MCU1") (pin "P13") (pinfunction "VDDA_P13") (pintype "bidirectional"))
      (node (ref "MCU1") (pin "P19") (pinfunction "VDD1_P19") (pintype "bidirectional"))
      (node (ref "MCU1") (pin "P32") (pinfunction "VDD2_P32") (pintype "bidirectional"))
      (node (ref "MCU1") (pin "P48") (pinfunction "VDD3_P48") (pintype "bidirectional"))
      (node (ref "MCU1") (pin "P64") (pinfunction "VDD4_P64") (pintype "bidirectional"))
      (node (ref "R1") (pin "P$2") (pinfunction "2_P$2") (pintype "passive"))
      (node (ref "U2") (pin "P5") (pinfunction "VOUT_P5") (pintype "bidirectional"))
      (node (ref "U3") (pin "P2") (pinfunction "SDX_P2") (pintype "bidirectional"))
      (node (ref "U3") (pin "P3") (pinfunction "SCX_P3") (pintype "bidirectional"))
      (node (ref "U3") (pin "P5") (pinfunction "VDDIO_P5") (pintype "bidirectional"))
      (node (ref "U3") (pin "P8") (pinfunction "VDD_P8") (pintype "bidirectional"))
      (node (ref "U4") (pin "P1") (pinfunction "VDD_P1") (pintype "bidirectional"))
      (node (ref "U4") (pin "P6") (pinfunction "CS_P6") (pintype "bidirectional"))
      (node (ref "U5") (pin "P1") (pinfunction "VDD_IO_P1") (pintype "bidirectional"))
      (node (ref "U5") (pin "P10") (pinfunction "VDD_P10") (pintype "bidirectional"))
      (node (ref "U5") (pin "P6") (pinfunction "CS_P6") (pintype "bidirectional"))
    )
    (net (code "55") (name "VUSB") (class "Default")
      (node (ref "C7") (pin "P$1") (pinfunction "1_P$1") (pintype "passive"))
      (node (ref "CN2") (pin "P1") (pinfunction "P1_P1") (pintype "bidirectional"))
      (node (ref "U8") (pin "4") (pinfunction "VDD_4") (pintype "bidirectional"))
    )
    (net (code "56") (name "unconnected-(CN2-PadP4)") (class "Default")
      (node (ref "CN2") (pin "P4") (pinfunction "P4_P4") (pintype "bidirectional"))
    )
    (net (code "57") (name "unconnected-(MCU1-PA8-PadP41)") (class "Default")
      (node (ref "MCU1") (pin "P41") (pinfunction "PA8_P41") (pintype "bidirectional"))
    )
    (net (code "58") (name "unconnected-(MCU1-PB5-PadP57)") (class "Default")
      (node (ref "MCU1") (pin "P57") (pinfunction "PB5_P57") (pintype "bidirectional"))
    )
    (net (code "59") (name "unconnected-(MCU1-PB8-PadP61)") (class "Default")
      (node (ref "MCU1") (pin "P61") (pinfunction "PB8_P61") (pintype "bidirectional"))
    )
    (net (code "60") (name "unconnected-(MCU1-PB9-PadP62)") (class "Default")
      (node (ref "MCU1") (pin "P62") (pinfunction "PB9_P62") (pintype "bidirectional"))
    )
    (net (code "61") (name "unconnected-(MCU1-PB15-PadP36)") (class "Default")
      (node (ref "MCU1") (pin "P36") (pinfunction "PB15_P36") (pintype "bidirectional"))
    )
    (net (code "62") (name "unconnected-(MCU1-PC6-PadP37)") (class "Default")
      (node (ref "MCU1") (pin "P37") (pinfunction "PC6_P37") (pintype "bidirectional"))
    )
    (net (code "63") (name "unconnected-(MCU1-PC7-PadP38)") (class "Default")
      (node (ref "MCU1") (pin "P38") (pinfunction "PC7_P38") (pintype "bidirectional"))
    )
    (net (code "64") (name "unconnected-(MCU1-PH0-PadP5)") (class "Default")
      (node (ref "MCU1") (pin "P5") (pinfunction "PH0_P5") (pintype "bidirectional"))
    )
    (net (code "65") (name "unconnected-(MCU1-PH1-PadP6)") (class "Default")
      (node (ref "MCU1") (pin "P6") (pinfunction "PH1_P6") (pintype "bidirectional"))
    )
    (net (code "66") (name "unconnected-(U1-{slash}ALRT-PadP5)") (class "Default")
      (node (ref "U1") (pin "P5") (pinfunction "/ALRT_P5") (pintype "bidirectional"))
    )
    (net (code "67") (name "unconnected-(U3-INT2-PadP9)") (class "Default")
      (node (ref "U3") (pin "P9") (pinfunction "INT2_P9") (pintype "bidirectional"))
    )
    (net (code "68") (name "unconnected-(U3-NC-PadP11)") (class "Default")
      (node (ref "U3") (pin "P11") (pinfunction "NC_P11") (pintype "bidirectional"))
    )
    (net (code "69") (name "unconnected-(U3-OCS-PadP10)") (class "Default")
      (node (ref "U3") (pin "P10") (pinfunction "OCS_P10") (pintype "bidirectional"))
    )
    (net (code "70") (name "unconnected-(U4-DRDY-PadP3)") (class "Default")
      (node (ref "U4") (pin "P3") (pinfunction "DRDY_P3") (pintype "bidirectional"))
    )
    (net (code "71") (name "unconnected-(U5-INT{slash}DRDY-PadP7)") (class "Default")
      (node (ref "U5") (pin "P7") (pinfunction "INT/DRDY_P7") (pintype "bidirectional"))
    )
    (net (code "72") (name "unconnected-(U6-EXT_LPCLK-PadP$1)") (class "Default")
      (node (ref "U6") (pin "P$1") (pinfunction "EXT_LPCLK_P$1") (pintype "bidirectional"))
    )
    (net (code "73") (name "unconnected-(U6-GPIO-PadP$2)") (class "Default")
      (node (ref "U6") (pin "P$2") (pinfunction "GPIO_P$2") (pintype "bidirectional"))
    )
    (net (code "74") (name "unconnected-(U6-TEST-PadP$3)") (class "Default")
      (node (ref "U6") (pin "P$3") (pinfunction "TEST_P$3") (pintype "bidirectional"))
    )
  )
)
